# untitled.net
KiCad netlist of a schematic drawn in EAGLE
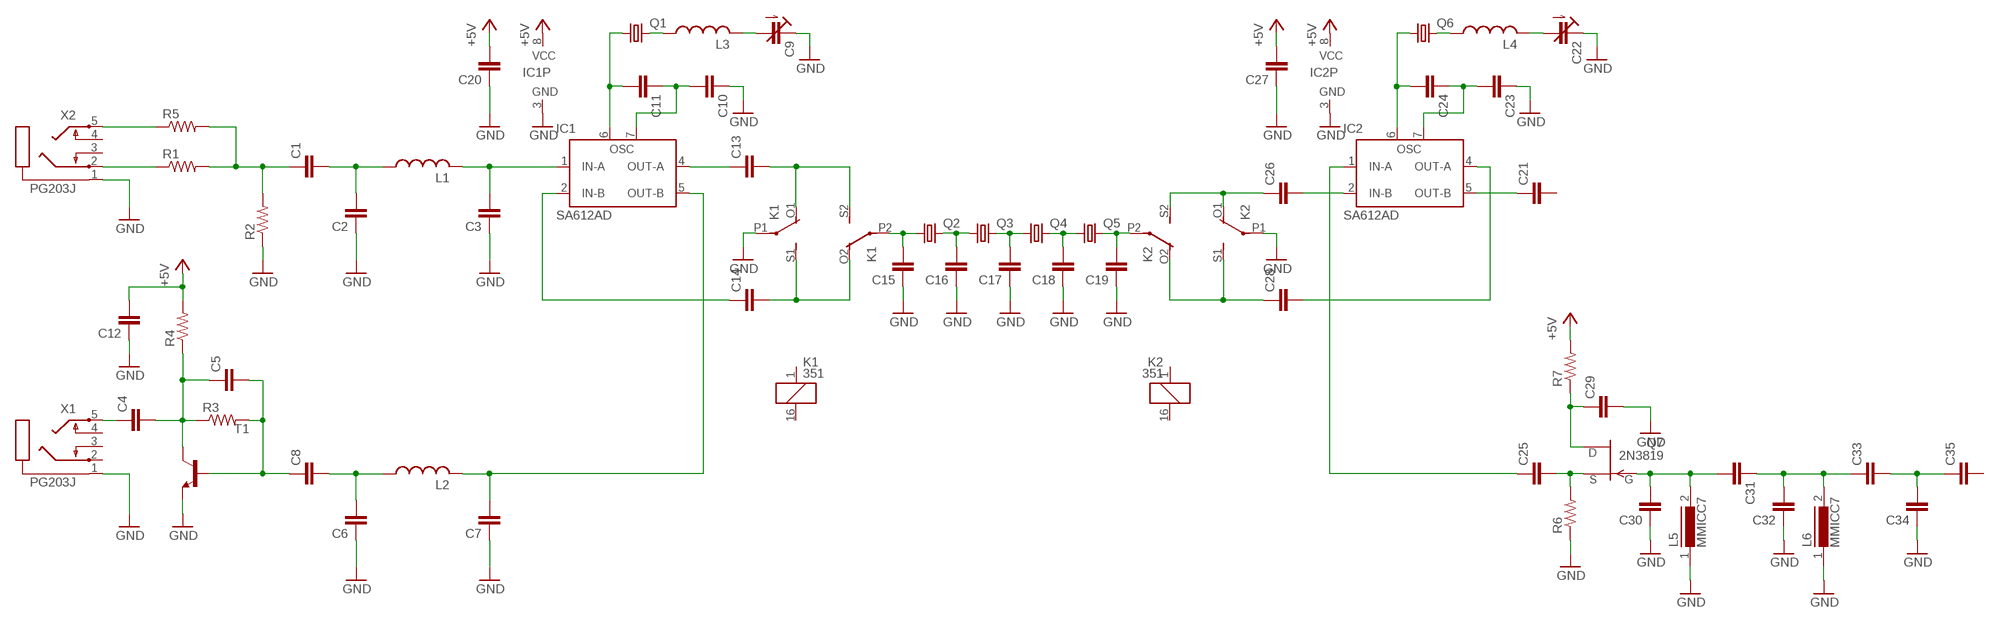
[diagram p0: schematic, sheet 1]

(export (version "E")
  (design (tool "Eeschema 10.0.6"))
  (components
    (comp (ref "C1")
      (value "C-EUC0805K")
      (footprint "eagle-import:C0805K")
      (libsource (lib "eagle-import") (part "C-EUC0805K"))
    )
    (comp (ref "C2")
      (value "C-EUC0805K")
      (footprint "eagle-import:C0805K")
      (libsource (lib "eagle-import") (part "C-EUC0805K"))
    )
    (comp (ref "C3")
      (value "C-EUC0805K")
      (footprint "eagle-import:C0805K")
      (libsource (lib "eagle-import") (part "C-EUC0805K"))
    )
    (comp (ref "C4")
      (value "C-EUC0805K")
      (footprint "eagle-import:C0805K")
      (libsource (lib "eagle-import") (part "C-EUC0805K"))
    )
    (comp (ref "C5")
      (value "C-EUC0805K")
      (footprint "eagle-import:C0805K")
      (libsource (lib "eagle-import") (part "C-EUC0805K"))
    )
    (comp (ref "C6")
      (value "C-EUC0805K")
      (footprint "eagle-import:C0805K")
      (libsource (lib "eagle-import") (part "C-EUC0805K"))
    )
    (comp (ref "C7")
      (value "C-EUC0805K")
      (footprint "eagle-import:C0805K")
      (libsource (lib "eagle-import") (part "C-EUC0805K"))
    )
    (comp (ref "C8")
      (value "C-EUC0805K")
      (footprint "eagle-import:C0805K")
      (libsource (lib "eagle-import") (part "C-EUC0805K"))
    )
    (comp (ref "C9")
      (value "C-TRIMMTZ03")
      (footprint "eagle-import:CTRIMTZ03")
      (libsource (lib "eagle-import") (part "C-TRIMMTZ03"))
    )
    (comp (ref "C10")
      (value "C-EUC0805K")
      (footprint "eagle-import:C0805K")
      (libsource (lib "eagle-import") (part "C-EUC0805K"))
    )
    (comp (ref "C11")
      (value "C-EUC0805K")
      (footprint "eagle-import:C0805K")
      (libsource (lib "eagle-import") (part "C-EUC0805K"))
    )
    (comp (ref "C12")
      (value "C-EUC0805K")
      (footprint "eagle-import:C0805K")
      (libsource (lib "eagle-import") (part "C-EUC0805K"))
    )
    (comp (ref "C13")
      (value "C-EUC0805K")
      (footprint "eagle-import:C0805K")
      (libsource (lib "eagle-import") (part "C-EUC0805K"))
    )
    (comp (ref "C14")
      (value "C-EUC0805K")
      (footprint "eagle-import:C0805K")
      (libsource (lib "eagle-import") (part "C-EUC0805K"))
    )
    (comp (ref "C15")
      (value "C-EUC0805K")
      (footprint "eagle-import:C0805K")
      (libsource (lib "eagle-import") (part "C-EUC0805K"))
    )
    (comp (ref "C16")
      (value "C-EUC0805K")
      (footprint "eagle-import:C0805K")
      (libsource (lib "eagle-import") (part "C-EUC0805K"))
    )
    (comp (ref "C17")
      (value "C-EUC0805K")
      (footprint "eagle-import:C0805K")
      (libsource (lib "eagle-import") (part "C-EUC0805K"))
    )
    (comp (ref "C18")
      (value "C-EUC0805K")
      (footprint "eagle-import:C0805K")
      (libsource (lib "eagle-import") (part "C-EUC0805K"))
    )
    (comp (ref "C19")
      (value "C-EUC0805K")
      (footprint "eagle-import:C0805K")
      (libsource (lib "eagle-import") (part "C-EUC0805K"))
    )
    (comp (ref "C20")
      (value "C-EUC0805K")
      (footprint "eagle-import:C0805K")
      (libsource (lib "eagle-import") (part "C-EUC0805K"))
    )
    (comp (ref "C21")
      (value "C-EUC0805K")
      (footprint "eagle-import:C0805K")
      (libsource (lib "eagle-import") (part "C-EUC0805K"))
    )
    (comp (ref "C22")
      (value "C-TRIMMTZ03")
      (footprint "eagle-import:CTRIMTZ03")
      (libsource (lib "eagle-import") (part "C-TRIMMTZ03"))
    )
    (comp (ref "C23")
      (value "C-EUC0805K")
      (footprint "eagle-import:C0805K")
      (libsource (lib "eagle-import") (part "C-EUC0805K"))
    )
    (comp (ref "C24")
      (value "C-EUC0805K")
      (footprint "eagle-import:C0805K")
      (libsource (lib "eagle-import") (part "C-EUC0805K"))
    )
    (comp (ref "C25")
      (value "C-EUC0805K")
      (footprint "eagle-import:C0805K")
      (libsource (lib "eagle-import") (part "C-EUC0805K"))
    )
    (comp (ref "C26")
      (value "C-EUC0805K")
      (footprint "eagle-import:C0805K")
      (libsource (lib "eagle-import") (part "C-EUC0805K"))
    )
    (comp (ref "C27")
      (value "C-EUC0805K")
      (footprint "eagle-import:C0805K")
      (libsource (lib "eagle-import") (part "C-EUC0805K"))
    )
    (comp (ref "C28")
      (value "C-EUC0805K")
      (footprint "eagle-import:C0805K")
      (libsource (lib "eagle-import") (part "C-EUC0805K"))
    )
    (comp (ref "C29")
      (value "C-EUC0805K")
      (footprint "eagle-import:C0805K")
      (libsource (lib "eagle-import") (part "C-EUC0805K"))
    )
    (comp (ref "C30")
      (value "C-EUC0805K")
      (footprint "eagle-import:C0805K")
      (libsource (lib "eagle-import") (part "C-EUC0805K"))
    )
    (comp (ref "C31")
      (value "C-EUC0805K")
      (footprint "eagle-import:C0805K")
      (libsource (lib "eagle-import") (part "C-EUC0805K"))
    )
    (comp (ref "C32")
      (value "C-EUC0805K")
      (footprint "eagle-import:C0805K")
      (libsource (lib "eagle-import") (part "C-EUC0805K"))
    )
    (comp (ref "C33")
      (value "C-EUC0805K")
      (footprint "eagle-import:C0805K")
      (libsource (lib "eagle-import") (part "C-EUC0805K"))
    )
    (comp (ref "C34")
      (value "C-EUC0805K")
      (footprint "eagle-import:C0805K")
      (libsource (lib "eagle-import") (part "C-EUC0805K"))
    )
    (comp (ref "C35")
      (value "C-EUC0805K")
      (footprint "eagle-import:C0805K")
      (libsource (lib "eagle-import") (part "C-EUC0805K"))
    )
    (comp (ref "IC1")
      (value "SA612AD")
      (footprint "eagle-import:SO08")
      (libsource (lib "eagle-import") (part "SA612AD"))
    )
    (comp (ref "IC2")
      (value "SA612AD")
      (footprint "eagle-import:SO08")
      (libsource (lib "eagle-import") (part "SA612AD"))
    )
    (comp (ref "K1")
      (value "351")
      (footprint "eagle-import:351")
      (libsource (lib "eagle-import") (part "351"))
    )
    (comp (ref "K2")
      (value "351")
      (footprint "eagle-import:351")
      (libsource (lib "eagle-import") (part "351"))
    )
    (comp (ref "L1")
      (value "L-US0204/7")
      (footprint "eagle-import:0204_7")
      (libsource (lib "eagle-import") (part "L-US0204/7"))
    )
    (comp (ref "L2")
      (value "L-US0204/7")
      (footprint "eagle-import:0204_7")
      (libsource (lib "eagle-import") (part "L-US0204/7"))
    )
    (comp (ref "L3")
      (value "L-US0204/7")
      (footprint "eagle-import:0204_7")
      (libsource (lib "eagle-import") (part "L-US0204/7"))
    )
    (comp (ref "L4")
      (value "L-US0204/7")
      (footprint "eagle-import:0204_7")
      (libsource (lib "eagle-import") (part "L-US0204/7"))
    )
    (comp (ref "L5")
      (value "MMICC7")
      (footprint "eagle-import:MMICC7")
      (libsource (lib "eagle-import") (part "MMICC7"))
    )
    (comp (ref "L6")
      (value "MMICC7")
      (footprint "eagle-import:MMICC7")
      (libsource (lib "eagle-import") (part "MMICC7"))
    )
    (comp (ref "Q1")
      (value "CRYSTALHC49S")
      (footprint "eagle-import:HC49_S")
      (libsource (lib "eagle-import") (part "CRYSTALHC49S"))
    )
    (comp (ref "Q2")
      (value "CRYSTALHC49S")
      (footprint "eagle-import:HC49_S")
      (libsource (lib "eagle-import") (part "CRYSTALHC49S"))
    )
    (comp (ref "Q3")
      (value "CRYSTALHC49S")
      (footprint "eagle-import:HC49_S")
      (libsource (lib "eagle-import") (part "CRYSTALHC49S"))
    )
    (comp (ref "Q4")
      (value "CRYSTALHC49S")
      (footprint "eagle-import:HC49_S")
      (libsource (lib "eagle-import") (part "CRYSTALHC49S"))
    )
    (comp (ref "Q5")
      (value "CRYSTALHC49S")
      (footprint "eagle-import:HC49_S")
      (libsource (lib "eagle-import") (part "CRYSTALHC49S"))
    )
    (comp (ref "Q6")
      (value "CRYSTALHC49S")
      (footprint "eagle-import:HC49_S")
      (libsource (lib "eagle-import") (part "CRYSTALHC49S"))
    )
    (comp (ref "Q7")
      (value "2N3819")
      (footprint "eagle-import:TO92")
      (libsource (lib "eagle-import") (part "2N3819"))
    )
    (comp (ref "R1")
      (value "R-US_R0805")
      (footprint "eagle-import:R0805")
      (libsource (lib "eagle-import") (part "R-US_R0805"))
    )
    (comp (ref "R2")
      (value "R-US_R0805")
      (footprint "eagle-import:R0805")
      (libsource (lib "eagle-import") (part "R-US_R0805"))
    )
    (comp (ref "R3")
      (value "R-US_R0805")
      (footprint "eagle-import:R0805")
      (libsource (lib "eagle-import") (part "R-US_R0805"))
    )
    (comp (ref "R4")
      (value "R-US_R0805")
      (footprint "eagle-import:R0805")
      (libsource (lib "eagle-import") (part "R-US_R0805"))
    )
    (comp (ref "R5")
      (value "R-US_R0805")
      (footprint "eagle-import:R0805")
      (libsource (lib "eagle-import") (part "R-US_R0805"))
    )
    (comp (ref "R6")
      (value "R-US_R0805")
      (footprint "eagle-import:R0805")
      (libsource (lib "eagle-import") (part "R-US_R0805"))
    )
    (comp (ref "R7")
      (value "R-US_R0805")
      (footprint "eagle-import:R0805")
      (libsource (lib "eagle-import") (part "R-US_R0805"))
    )
    (comp (ref "T1")
      (value "MMBT3904LT1-NPN-SOT23-BEC")
      (footprint "eagle-import:SOT23-BEC")
      (libsource (lib "eagle-import") (part "-NPN-SOT23-BECMMBT3904LT1"))
    )
    (comp (ref "X1")
      (value "PG203J")
      (footprint "eagle-import:PG203J")
      (libsource (lib "eagle-import") (part "PG203J"))
    )
    (comp (ref "X2")
      (value "PG203J")
      (footprint "eagle-import:PG203J")
      (libsource (lib "eagle-import") (part "PG203J"))
    )
  )
  (nets
    (net (code "1") (name "+5V") (class "Default")
      (node (ref "C12") (pin "2") (pinfunction "2_2") (pintype "passive"))
      (node (ref "C20") (pin "2") (pinfunction "2_2") (pintype "passive"))
      (node (ref "C27") (pin "2") (pinfunction "2_2") (pintype "passive"))
      (node (ref "IC1") (pin "8") (pinfunction "VCC_8") (pintype "power_in"))
      (node (ref "IC2") (pin "8") (pinfunction "VCC_8") (pintype "power_in"))
      (node (ref "R4") (pin "2") (pinfunction "2_2") (pintype "passive"))
      (node (ref "R7") (pin "2") (pinfunction "2_2") (pintype "passive"))
    )
    (net (code "2") (name "GND") (class "Default")
      (node (ref "C10") (pin "1") (pinfunction "1_1") (pintype "passive"))
      (node (ref "C12") (pin "1") (pinfunction "1_1") (pintype "passive"))
      (node (ref "C15") (pin "1") (pinfunction "1_1") (pintype "passive"))
      (node (ref "C16") (pin "1") (pinfunction "1_1") (pintype "passive"))
      (node (ref "C17") (pin "1") (pinfunction "1_1") (pintype "passive"))
      (node (ref "C18") (pin "1") (pinfunction "1_1") (pintype "passive"))
      (node (ref "C19") (pin "1") (pinfunction "1_1") (pintype "passive"))
      (node (ref "C2") (pin "1") (pinfunction "1_1") (pintype "passive"))
      (node (ref "C20") (pin "1") (pinfunction "1_1") (pintype "passive"))
      (node (ref "C22") (pin "1") (pinfunction "E_1") (pintype "passive"))
      (node (ref "C23") (pin "1") (pinfunction "1_1") (pintype "passive"))
      (node (ref "C27") (pin "1") (pinfunction "1_1") (pintype "passive"))
      (node (ref "C29") (pin "2") (pinfunction "2_2") (pintype "passive"))
      (node (ref "C3") (pin "1") (pinfunction "1_1") (pintype "passive"))
      (node (ref "C30") (pin "1") (pinfunction "1_1") (pintype "passive"))
      (node (ref "C32") (pin "1") (pinfunction "1_1") (pintype "passive"))
      (node (ref "C34") (pin "1") (pinfunction "1_1") (pintype "passive"))
      (node (ref "C6") (pin "1") (pinfunction "1_1") (pintype "passive"))
      (node (ref "C7") (pin "1") (pinfunction "1_1") (pintype "passive"))
      (node (ref "C9") (pin "1") (pinfunction "E_1") (pintype "passive"))
      (node (ref "IC1") (pin "3") (pinfunction "GND_3") (pintype "power_in"))
      (node (ref "IC2") (pin "3") (pinfunction "GND_3") (pintype "power_in"))
      (node (ref "K1") (pin "P1") (pinfunction "P_P1") (pintype "passive"))
      (node (ref "K2") (pin "P1") (pinfunction "P_P1") (pintype "passive"))
      (node (ref "L5") (pin "1") (pinfunction "1_1") (pintype "passive"))
      (node (ref "L6") (pin "1") (pinfunction "1_1") (pintype "passive"))
      (node (ref "R2") (pin "1") (pinfunction "1_1") (pintype "passive"))
      (node (ref "R6") (pin "1") (pinfunction "1_1") (pintype "passive"))
      (node (ref "T1") (pin "E") (pinfunction "E_E") (pintype "passive"))
      (node (ref "X1") (pin "1") (pinfunction "1_1") (pintype "passive"))
      (node (ref "X2") (pin "1") (pinfunction "1_1") (pintype "passive"))
    )
    (net (code "3") (name "Net-(C1-Pad1)") (class "Default")
      (node (ref "C1") (pin "1") (pinfunction "1_1") (pintype "passive"))
      (node (ref "R1") (pin "2") (pinfunction "2_2") (pintype "passive"))
      (node (ref "R2") (pin "2") (pinfunction "2_2") (pintype "passive"))
      (node (ref "R5") (pin "2") (pinfunction "2_2") (pintype "passive"))
    )
    (net (code "4") (name "Net-(C1-Pad2)") (class "Default")
      (node (ref "C1") (pin "2") (pinfunction "2_2") (pintype "passive"))
      (node (ref "C2") (pin "2") (pinfunction "2_2") (pintype "passive"))
      (node (ref "L1") (pin "1") (pinfunction "1_1") (pintype "passive"))
    )
    (net (code "5") (name "Net-(C4-Pad1)") (class "Default")
      (node (ref "C4") (pin "1") (pinfunction "1_1") (pintype "passive"))
      (node (ref "X1") (pin "5") (pinfunction "5_5") (pintype "passive"))
    )
    (net (code "6") (name "Net-(C4-Pad2)") (class "Default")
      (node (ref "C4") (pin "2") (pinfunction "2_2") (pintype "passive"))
      (node (ref "C5") (pin "1") (pinfunction "1_1") (pintype "passive"))
      (node (ref "R3") (pin "1") (pinfunction "1_1") (pintype "passive"))
      (node (ref "R4") (pin "1") (pinfunction "1_1") (pintype "passive"))
      (node (ref "T1") (pin "C") (pinfunction "C_C") (pintype "passive"))
    )
    (net (code "7") (name "Net-(C5-Pad2)") (class "Default")
      (node (ref "C5") (pin "2") (pinfunction "2_2") (pintype "passive"))
      (node (ref "C8") (pin "1") (pinfunction "1_1") (pintype "passive"))
      (node (ref "R3") (pin "2") (pinfunction "2_2") (pintype "passive"))
      (node (ref "T1") (pin "B") (pinfunction "B_B") (pintype "passive"))
    )
    (net (code "8") (name "Net-(C6-Pad2)") (class "Default")
      (node (ref "C6") (pin "2") (pinfunction "2_2") (pintype "passive"))
      (node (ref "C8") (pin "2") (pinfunction "2_2") (pintype "passive"))
      (node (ref "L2") (pin "1") (pinfunction "1_1") (pintype "passive"))
    )
    (net (code "9") (name "Net-(C9-A)") (class "Default")
      (node (ref "C9") (pin "2") (pinfunction "A_2") (pintype "passive"))
      (node (ref "L3") (pin "2") (pinfunction "2_2") (pintype "passive"))
    )
    (net (code "10") (name "Net-(C16-Pad2)") (class "Default")
      (node (ref "C16") (pin "2") (pinfunction "2_2") (pintype "passive"))
      (node (ref "Q2") (pin "2") (pinfunction "2_2") (pintype "passive"))
      (node (ref "Q3") (pin "1") (pinfunction "1_1") (pintype "passive"))
    )
    (net (code "11") (name "Net-(C17-Pad2)") (class "Default")
      (node (ref "C17") (pin "2") (pinfunction "2_2") (pintype "passive"))
      (node (ref "Q3") (pin "2") (pinfunction "2_2") (pintype "passive"))
      (node (ref "Q4") (pin "1") (pinfunction "1_1") (pintype "passive"))
    )
    (net (code "12") (name "Net-(C18-Pad2)") (class "Default")
      (node (ref "C18") (pin "2") (pinfunction "2_2") (pintype "passive"))
      (node (ref "Q4") (pin "2") (pinfunction "2_2") (pintype "passive"))
      (node (ref "Q5") (pin "1") (pinfunction "1_1") (pintype "passive"))
    )
    (net (code "13") (name "Net-(C22-A)") (class "Default")
      (node (ref "C22") (pin "2") (pinfunction "A_2") (pintype "passive"))
      (node (ref "L4") (pin "2") (pinfunction "2_2") (pintype "passive"))
    )
    (net (code "14") (name "Net-(C31-Pad1)") (class "Default")
      (node (ref "C31") (pin "1") (pinfunction "1_1") (pintype "passive"))
      (node (ref "C32") (pin "2") (pinfunction "2_2") (pintype "passive"))
      (node (ref "C33") (pin "1") (pinfunction "1_1") (pintype "passive"))
      (node (ref "L6") (pin "2") (pinfunction "2_2") (pintype "passive"))
    )
    (net (code "15") (name "Net-(C33-Pad2)") (class "Default")
      (node (ref "C33") (pin "2") (pinfunction "2_2") (pintype "passive"))
      (node (ref "C34") (pin "2") (pinfunction "2_2") (pintype "passive"))
      (node (ref "C35") (pin "1") (pinfunction "1_1") (pintype "passive"))
    )
    (net (code "16") (name "Net-(IC1A-IN-A)") (class "Default")
      (node (ref "C3") (pin "2") (pinfunction "2_2") (pintype "passive"))
      (node (ref "IC1") (pin "1") (pinfunction "IN-A_1") (pintype "input"))
      (node (ref "L1") (pin "2") (pinfunction "2_2") (pintype "passive"))
    )
    (net (code "17") (name "Net-(IC1A-IN-B)") (class "Default")
      (node (ref "C14") (pin "1") (pinfunction "1_1") (pintype "passive"))
      (node (ref "IC1") (pin "2") (pinfunction "IN-B_2") (pintype "input"))
    )
    (net (code "18") (name "Net-(IC1A-OSC')") (class "Default")
      (node (ref "C10") (pin "2") (pinfunction "2_2") (pintype "passive"))
      (node (ref "C11") (pin "1") (pinfunction "1_1") (pintype "passive"))
      (node (ref "IC1") (pin "7") (pinfunction "OSC'_7") (pintype "passive"))
    )
    (net (code "19") (name "Net-(IC1A-OSC)") (class "Default")
      (node (ref "C11") (pin "2") (pinfunction "2_2") (pintype "passive"))
      (node (ref "IC1") (pin "6") (pinfunction "OSC_6") (pintype "passive"))
      (node (ref "Q1") (pin "1") (pinfunction "1_1") (pintype "passive"))
    )
    (net (code "20") (name "Net-(IC1A-OUT-A)") (class "Default")
      (node (ref "C13") (pin "1") (pinfunction "1_1") (pintype "passive"))
      (node (ref "IC1") (pin "4") (pinfunction "OUT-A_4") (pintype "input"))
    )
    (net (code "21") (name "Net-(IC1A-OUT-B)") (class "Default")
      (node (ref "C7") (pin "2") (pinfunction "2_2") (pintype "passive"))
      (node (ref "IC1") (pin "5") (pinfunction "OUT-B_5") (pintype "input"))
      (node (ref "L2") (pin "2") (pinfunction "2_2") (pintype "passive"))
    )
    (net (code "22") (name "Net-(IC2A-IN-A)") (class "Default")
      (node (ref "C25") (pin "1") (pinfunction "1_1") (pintype "passive"))
      (node (ref "IC2") (pin "1") (pinfunction "IN-A_1") (pintype "input"))
    )
    (net (code "23") (name "Net-(IC2A-IN-B)") (class "Default")
      (node (ref "C26") (pin "2") (pinfunction "2_2") (pintype "passive"))
      (node (ref "IC2") (pin "2") (pinfunction "IN-B_2") (pintype "input"))
    )
    (net (code "24") (name "Net-(IC2A-OSC')") (class "Default")
      (node (ref "C23") (pin "2") (pinfunction "2_2") (pintype "passive"))
      (node (ref "C24") (pin "1") (pinfunction "1_1") (pintype "passive"))
      (node (ref "IC2") (pin "7") (pinfunction "OSC'_7") (pintype "passive"))
    )
    (net (code "25") (name "Net-(IC2A-OSC)") (class "Default")
      (node (ref "C24") (pin "2") (pinfunction "2_2") (pintype "passive"))
      (node (ref "IC2") (pin "6") (pinfunction "OSC_6") (pintype "passive"))
      (node (ref "Q6") (pin "1") (pinfunction "1_1") (pintype "passive"))
    )
    (net (code "26") (name "Net-(IC2A-OUT-A)") (class "Default")
      (node (ref "C28") (pin "2") (pinfunction "2_2") (pintype "passive"))
      (node (ref "IC2") (pin "4") (pinfunction "OUT-A_4") (pintype "input"))
    )
    (net (code "27") (name "Net-(IC2A-OUT-B)") (class "Default")
      (node (ref "C21") (pin "1") (pinfunction "1_1") (pintype "passive"))
      (node (ref "IC2") (pin "5") (pinfunction "OUT-B_5") (pintype "input"))
    )
    (net (code "28") (name "Net-(K1B-O)") (class "Default")
      (node (ref "C13") (pin "2") (pinfunction "2_2") (pintype "passive"))
      (node (ref "K1") (pin "O1") (pinfunction "O_O1") (pintype "passive"))
      (node (ref "K1") (pin "S2") (pinfunction "S_S2") (pintype "passive"))
    )
    (net (code "29") (name "Net-(K1B-S)") (class "Default")
      (node (ref "C14") (pin "2") (pinfunction "2_2") (pintype "passive"))
      (node (ref "K1") (pin "O2") (pinfunction "O_O2") (pintype "passive"))
      (node (ref "K1") (pin "S1") (pinfunction "S_S1") (pintype "passive"))
    )
    (net (code "30") (name "Net-(K1C-P)") (class "Default")
      (node (ref "C15") (pin "2") (pinfunction "2_2") (pintype "passive"))
      (node (ref "K1") (pin "P2") (pinfunction "P_P2") (pintype "passive"))
      (node (ref "Q2") (pin "1") (pinfunction "1_1") (pintype "passive"))
    )
    (net (code "31") (name "Net-(K2B-O)") (class "Default")
      (node (ref "C26") (pin "1") (pinfunction "1_1") (pintype "passive"))
      (node (ref "K2") (pin "O1") (pinfunction "O_O1") (pintype "passive"))
      (node (ref "K2") (pin "S2") (pinfunction "S_S2") (pintype "passive"))
    )
    (net (code "32") (name "Net-(K2B-S)") (class "Default")
      (node (ref "C28") (pin "1") (pinfunction "1_1") (pintype "passive"))
      (node (ref "K2") (pin "O2") (pinfunction "O_O2") (pintype "passive"))
      (node (ref "K2") (pin "S1") (pinfunction "S_S1") (pintype "passive"))
    )
    (net (code "33") (name "Net-(K2C-P)") (class "Default")
      (node (ref "C19") (pin "2") (pinfunction "2_2") (pintype "passive"))
      (node (ref "K2") (pin "P2") (pinfunction "P_P2") (pintype "passive"))
      (node (ref "Q5") (pin "2") (pinfunction "2_2") (pintype "passive"))
    )
    (net (code "34") (name "Net-(L3-Pad1)") (class "Default")
      (node (ref "L3") (pin "1") (pinfunction "1_1") (pintype "passive"))
      (node (ref "Q1") (pin "2") (pinfunction "2_2") (pintype "passive"))
    )
    (net (code "35") (name "Net-(L4-Pad1)") (class "Default")
      (node (ref "L4") (pin "1") (pinfunction "1_1") (pintype "passive"))
      (node (ref "Q6") (pin "2") (pinfunction "2_2") (pintype "passive"))
    )
    (net (code "36") (name "Net-(Q7-D)") (class "Default")
      (node (ref "C29") (pin "1") (pinfunction "1_1") (pintype "passive"))
      (node (ref "Q7") (pin "1") (pinfunction "D_1") (pintype "passive"))
      (node (ref "R7") (pin "1") (pinfunction "1_1") (pintype "passive"))
    )
    (net (code "37") (name "Net-(Q7-G)") (class "Default")
      (node (ref "C30") (pin "2") (pinfunction "2_2") (pintype "passive"))
      (node (ref "C31") (pin "2") (pinfunction "2_2") (pintype "passive"))
      (node (ref "L5") (pin "2") (pinfunction "2_2") (pintype "passive"))
      (node (ref "Q7") (pin "2") (pinfunction "G_2") (pintype "passive"))
    )
    (net (code "38") (name "Net-(Q7-S)") (class "Default")
      (node (ref "C25") (pin "2") (pinfunction "2_2") (pintype "passive"))
      (node (ref "Q7") (pin "3") (pinfunction "S_3") (pintype "passive"))
      (node (ref "R6") (pin "2") (pinfunction "2_2") (pintype "passive"))
    )
    (net (code "39") (name "Net-(R1-Pad1)") (class "Default")
      (node (ref "R1") (pin "1") (pinfunction "1_1") (pintype "passive"))
      (node (ref "X2") (pin "2") (pinfunction "2_2") (pintype "passive"))
    )
    (net (code "40") (name "Net-(R5-Pad1)") (class "Default")
      (node (ref "R5") (pin "1") (pinfunction "1_1") (pintype "passive"))
      (node (ref "X2") (pin "5") (pinfunction "5_5") (pintype "passive"))
    )
    (net (code "41") (name "unconnected-(C21-Pad2)") (class "Default")
      (node (ref "C21") (pin "2") (pinfunction "2_2") (pintype "passive"))
    )
    (net (code "42") (name "unconnected-(C35-Pad2)") (class "Default")
      (node (ref "C35") (pin "2") (pinfunction "2_2") (pintype "passive"))
    )
    (net (code "43") (name "unconnected-(K1-Pad1)") (class "Default")
      (node (ref "K1") (pin "1") (pinfunction "1_1") (pintype "passive"))
    )
    (net (code "44") (name "unconnected-(K1A-2-Pad16)") (class "Default")
      (node (ref "K1") (pin "16") (pinfunction "2_16") (pintype "passive"))
    )
    (net (code "45") (name "unconnected-(K2-Pad1)") (class "Default")
      (node (ref "K2") (pin "1") (pinfunction "1_1") (pintype "passive"))
    )
    (net (code "46") (name "unconnected-(K2A-2-Pad16)") (class "Default")
      (node (ref "K2") (pin "16") (pinfunction "2_16") (pintype "passive"))
    )
    (net (code "47") (name "unconnected-(X1-Pad2)") (class "Default")
      (node (ref "X1") (pin "2") (pinfunction "2_2") (pintype "passive"))
    )
    (net (code "48") (name "unconnected-(X1-Pad3)") (class "Default")
      (node (ref "X1") (pin "3") (pinfunction "3_3") (pintype "passive"))
    )
    (net (code "49") (name "unconnected-(X1-Pad4)") (class "Default")
      (node (ref "X1") (pin "4") (pinfunction "4_4") (pintype "passive"))
    )
    (net (code "50") (name "unconnected-(X2-Pad3)") (class "Default")
      (node (ref "X2") (pin "3") (pinfunction "3_3") (pintype "passive"))
    )
    (net (code "51") (name "unconnected-(X2-Pad4)") (class "Default")
      (node (ref "X2") (pin "4") (pinfunction "4_4") (pintype "passive"))
    )
  )
)
